# prnet_v04_adxl362.net
KiCad netlist of a schematic drawn in Altium Designer
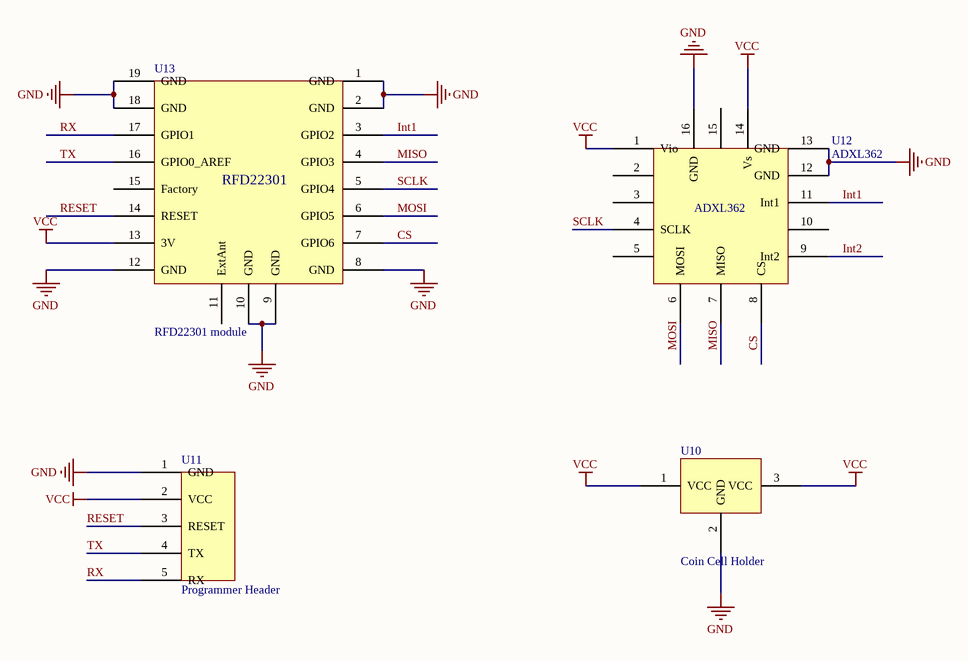
[diagram p0: prnet_v04_adxl362.SchDoc]

(export (version "E")
  (design (tool "Eeschema 10.0.6"))
  (components
    (comp (ref "U10")
      (value "Coin Cell Holder")
      (footprint "CoinCell")
      (libsource (lib "CoinCellHolder") (part "CoinCellHolder"))
    )
    (comp (ref "U11")
      (value "Programmer Header")
      (footprint "PrgHeader")
      (libsource (lib "ProgrammerHeader") (part "Component_1"))
    )
    (comp (ref "U12") (value "ADXL362") (footprint "ADXL362") (libsource (lib "ADXL362") (part "ADXL362")))
    (comp (ref "U13")
      (value "RFD22301 module")
      (footprint "RFD22301")
      (libsource (lib "RFD22301_Footprint") (part "RFD22301_Footprint"))
    )
  )
  (nets
    (net (code "1") (name "/CS") (class "Default")
      (node (ref "U12") (pin "8") (pinfunction "CS_8") (pintype "passive"))
      (node (ref "U13") (pin "7") (pinfunction "GPIO6_7") (pintype "passive"))
    )
    (net (code "2") (name "/Int1") (class "Default")
      (node (ref "U12") (pin "11") (pinfunction "Int1_11") (pintype "passive"))
      (node (ref "U13") (pin "3") (pinfunction "GPIO2_3") (pintype "passive"))
    )
    (net (code "3") (name "/Int2") (class "Default")
      (node (ref "U12") (pin "9") (pinfunction "Int2_9") (pintype "passive"))
    )
    (net (code "4") (name "/MISO") (class "Default")
      (node (ref "U12") (pin "7") (pinfunction "MISO_7") (pintype "passive"))
      (node (ref "U13") (pin "4") (pinfunction "GPIO3_4") (pintype "passive"))
    )
    (net (code "5") (name "/MOSI") (class "Default")
      (node (ref "U12") (pin "6") (pinfunction "MOSI_6") (pintype "passive"))
      (node (ref "U13") (pin "6") (pinfunction "GPIO5_6") (pintype "passive"))
    )
    (net (code "6") (name "/RESET") (class "Default")
      (node (ref "U11") (pin "3") (pinfunction "RESET_3") (pintype "passive"))
      (node (ref "U13") (pin "14") (pinfunction "RESET_14") (pintype "passive"))
    )
    (net (code "7") (name "/RX") (class "Default")
      (node (ref "U11") (pin "5") (pinfunction "RX_5") (pintype "passive"))
      (node (ref "U13") (pin "17") (pinfunction "GPIO1_17") (pintype "passive"))
    )
    (net (code "8") (name "/SCLK") (class "Default")
      (node (ref "U12") (pin "4") (pinfunction "SCLK_4") (pintype "passive"))
      (node (ref "U13") (pin "5") (pinfunction "GPIO4_5") (pintype "passive"))
    )
    (net (code "9") (name "/TX") (class "Default")
      (node (ref "U11") (pin "4") (pinfunction "TX_4") (pintype "passive"))
      (node (ref "U13") (pin "16") (pinfunction "GPIO0_AREF_16") (pintype "passive"))
    )
    (net (code "10") (name "GND") (class "Default")
      (node (ref "U10") (pin "2") (pinfunction "GND_2") (pintype "passive"))
      (node (ref "U11") (pin "1") (pinfunction "GND_1") (pintype "passive"))
      (node (ref "U12") (pin "12") (pinfunction "GND_12") (pintype "passive"))
      (node (ref "U12") (pin "13") (pinfunction "GND_13") (pintype "passive"))
      (node (ref "U12") (pin "16") (pinfunction "GND_16") (pintype "passive"))
      (node (ref "U13") (pin "1") (pinfunction "GND_1") (pintype "passive"))
      (node (ref "U13") (pin "10") (pinfunction "GND_10") (pintype "passive"))
      (node (ref "U13") (pin "12") (pinfunction "GND_12") (pintype "passive"))
      (node (ref "U13") (pin "18") (pinfunction "GND_18") (pintype "passive"))
      (node (ref "U13") (pin "19") (pinfunction "GND_19") (pintype "passive"))
      (node (ref "U13") (pin "2") (pinfunction "GND_2") (pintype "passive"))
      (node (ref "U13") (pin "8") (pinfunction "GND_8") (pintype "passive"))
      (node (ref "U13") (pin "9") (pinfunction "GND_9") (pintype "passive"))
    )
    (net (code "11") (name "VCC") (class "Default")
      (node (ref "U10") (pin "1") (pinfunction "VCC_1") (pintype "passive"))
      (node (ref "U10") (pin "3") (pinfunction "VCC_3") (pintype "passive"))
      (node (ref "U11") (pin "2") (pinfunction "VCC_2") (pintype "passive"))
      (node (ref "U12") (pin "1") (pinfunction "Vio_1") (pintype "passive"))
      (node (ref "U12") (pin "14") (pinfunction "Vs_14") (pintype "passive"))
      (node (ref "U13") (pin "13") (pinfunction "3V_13") (pintype "passive"))
    )
    (net (code "12") (name "unconnected-(U12-Pad2)") (class "Default")
      (node (ref "U12") (pin "2") (pintype "passive"))
    )
    (net (code "13") (name "unconnected-(U12-Pad3)") (class "Default")
      (node (ref "U12") (pin "3") (pintype "passive"))
    )
    (net (code "14") (name "unconnected-(U12-Pad5)") (class "Default")
      (node (ref "U12") (pin "5") (pintype "passive"))
    )
    (net (code "15") (name "unconnected-(U12-Pad10)") (class "Default")
      (node (ref "U12") (pin "10") (pintype "passive"))
    )
    (net (code "16") (name "unconnected-(U12-Pad15)") (class "Default")
      (node (ref "U12") (pin "15") (pintype "passive"))
    )
    (net (code "17") (name "unconnected-(U13-ExtAnt-Pad11)") (class "Default")
      (node (ref "U13") (pin "11") (pinfunction "ExtAnt_11") (pintype "passive"))
    )
    (net (code "18") (name "unconnected-(U13-Factory-Pad15)") (class "Default")
      (node (ref "U13") (pin "15") (pinfunction "Factory_15") (pintype "passive"))
    )
  )
)
